# netCPU_breakout.net
KiCad netlist of a schematic drawn in EAGLE
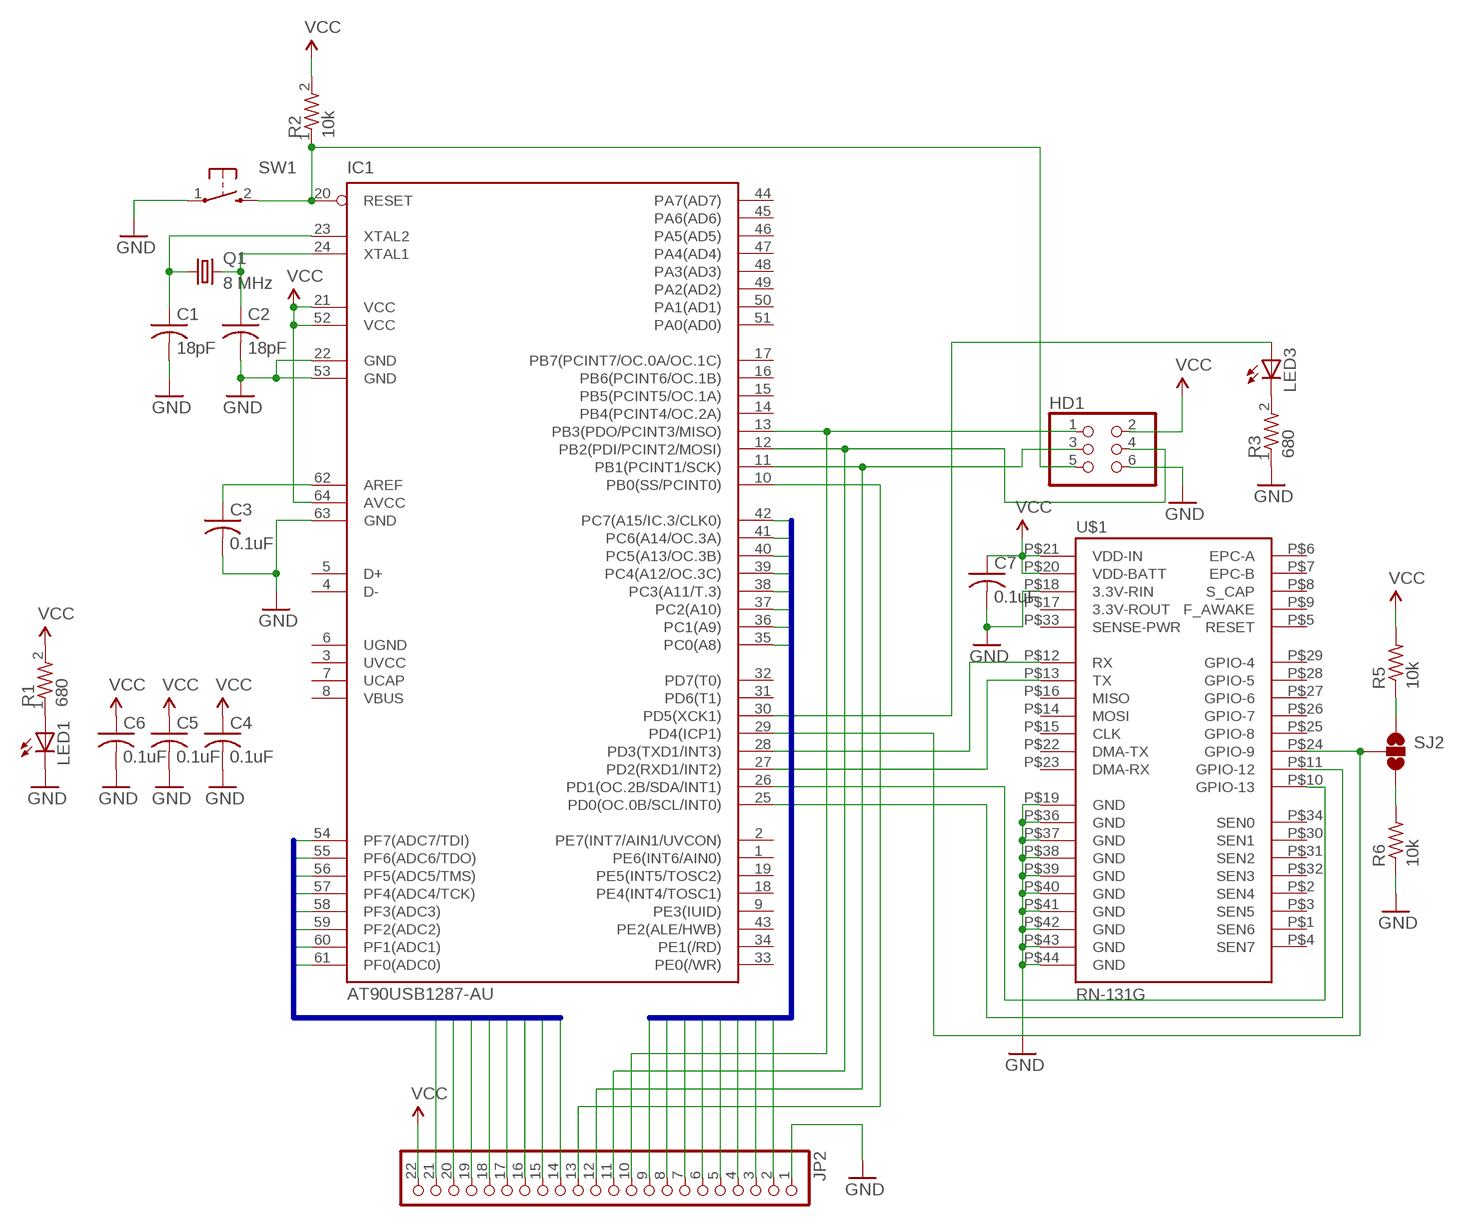
[diagram p0: schematic, sheet 1]

(export (version "E")
  (design (tool "Eeschema 10.0.6"))
  (components
    (comp (ref "C1")
      (value "18pF")
      (footprint "eagle-import:C0603K")
      (libsource (lib "eagle-import") (part "C-USC0603K"))
    )
    (comp (ref "C2")
      (value "18pF")
      (footprint "eagle-import:C0603K")
      (libsource (lib "eagle-import") (part "C-USC0603K"))
    )
    (comp (ref "C3")
      (value "0.1uF")
      (footprint "eagle-import:C0603K")
      (libsource (lib "eagle-import") (part "C-USC0603K"))
    )
    (comp (ref "C4")
      (value "0.1uF")
      (footprint "eagle-import:C0603K")
      (libsource (lib "eagle-import") (part "C-USC0603K"))
    )
    (comp (ref "C5")
      (value "0.1uF")
      (footprint "eagle-import:C0603K")
      (libsource (lib "eagle-import") (part "C-USC0603K"))
    )
    (comp (ref "C6")
      (value "0.1uF")
      (footprint "eagle-import:C0603K")
      (libsource (lib "eagle-import") (part "C-USC0603K"))
    )
    (comp (ref "C7")
      (value "0.1uF")
      (footprint "eagle-import:C0603K")
      (libsource (lib "eagle-import") (part "C-USC0603K"))
    )
    (comp (ref "HD1")
      (value "HEADER2X3")
      (footprint "eagle-import:HEADER2X3")
      (libsource (lib "eagle-import") (part "HEADER2X3"))
    )
    (comp (ref "IC1")
      (value "AT90USB1287-AU")
      (footprint "eagle-import:TQFP64")
      (libsource (lib "eagle-import") (part "AT90USB1287-AU"))
    )
    (comp (ref "JP2")
      (value "PINHD-1X22")
      (footprint "eagle-import:1X22")
      (libsource (lib "eagle-import") (part "PINHD-1X22"))
    )
    (comp (ref "LED1")
      (value "LEDCHIP-LED0603")
      (footprint "eagle-import:CHIP-LED0603")
      (libsource (lib "eagle-import") (part "LEDCHIP-LED0603"))
    )
    (comp (ref "LED3")
      (value "LEDCHIP-LED0603")
      (footprint "eagle-import:CHIP-LED0603")
      (libsource (lib "eagle-import") (part "LEDCHIP-LED0603"))
    )
    (comp (ref "Q1")
      (value "8 MHz")
      (footprint "eagle-import:HC49UP")
      (libsource (lib "eagle-import") (part "CRYSTALHC49UP"))
    )
    (comp (ref "R1")
      (value "680")
      (footprint "eagle-import:0603_RESISTOR")
      (libsource (lib "eagle-import") (part "0603_RESISTOR"))
    )
    (comp (ref "R2")
      (value "10k")
      (footprint "eagle-import:0603_RESISTOR")
      (libsource (lib "eagle-import") (part "0603_RESISTOR"))
    )
    (comp (ref "R3")
      (value "680")
      (footprint "eagle-import:0603_RESISTOR")
      (libsource (lib "eagle-import") (part "0603_RESISTOR"))
    )
    (comp (ref "R5")
      (value "10k")
      (footprint "eagle-import:R0603")
      (libsource (lib "eagle-import") (part "R-US_R0603"))
    )
    (comp (ref "R6")
      (value "10k")
      (footprint "eagle-import:R0603")
      (libsource (lib "eagle-import") (part "R-US_R0603"))
    )
    (comp (ref "SJ2")
      (value "SOLDERJUMPER_2WAYPASTE2&3")
      (footprint "eagle-import:SJ_3_PASTE2&3")
      (libsource (lib "eagle-import") (part "SOLDERJUMPER_2WAYPASTE2&3"))
    )
    (comp (ref "SW1")
      (value "TAC-SWITCH")
      (footprint "eagle-import:TAC-SWITCH")
      (libsource (lib "eagle-import") (part "TAC-SWITCH"))
    )
    (comp (ref "U$1")
      (value "RN-131G")
      (footprint "eagle-import:RN-131G")
      (libsource (lib "eagle-import") (part "RN-131G"))
    )
  )
  (nets
    (net (code "1") (name "/PC0") (class "Default")
      (node (ref "IC1") (pin "35") (pinfunction "PC0(A8)_35") (pintype "bidirectional"))
      (node (ref "JP2") (pin "2") (pinfunction "2_2") (pintype "passive"))
    )
    (net (code "2") (name "/PC1") (class "Default")
      (node (ref "IC1") (pin "36") (pinfunction "PC1(A9)_36") (pintype "bidirectional"))
      (node (ref "JP2") (pin "3") (pinfunction "3_3") (pintype "passive"))
    )
    (net (code "3") (name "/PC2") (class "Default")
      (node (ref "IC1") (pin "37") (pinfunction "PC2(A10)_37") (pintype "bidirectional"))
      (node (ref "JP2") (pin "4") (pinfunction "4_4") (pintype "passive"))
    )
    (net (code "4") (name "/PC3") (class "Default")
      (node (ref "IC1") (pin "38") (pinfunction "PC3(A11/T.3)_38") (pintype "bidirectional"))
      (node (ref "JP2") (pin "5") (pinfunction "5_5") (pintype "passive"))
    )
    (net (code "5") (name "/PC4") (class "Default")
      (node (ref "IC1") (pin "39") (pinfunction "PC4(A12/OC.3C)_39") (pintype "bidirectional"))
      (node (ref "JP2") (pin "6") (pinfunction "6_6") (pintype "passive"))
    )
    (net (code "6") (name "/PC5") (class "Default")
      (node (ref "IC1") (pin "40") (pinfunction "PC5(A13/OC.3B)_40") (pintype "bidirectional"))
      (node (ref "JP2") (pin "7") (pinfunction "7_7") (pintype "passive"))
    )
    (net (code "7") (name "/PC6") (class "Default")
      (node (ref "IC1") (pin "41") (pinfunction "PC6(A14/OC.3A)_41") (pintype "bidirectional"))
      (node (ref "JP2") (pin "8") (pinfunction "8_8") (pintype "passive"))
    )
    (net (code "8") (name "/PC7") (class "Default")
      (node (ref "IC1") (pin "42") (pinfunction "PC7(A15/IC.3/CLK0)_42") (pintype "bidirectional"))
      (node (ref "JP2") (pin "9") (pinfunction "9_9") (pintype "passive"))
    )
    (net (code "9") (name "/PF0") (class "Default")
      (node (ref "IC1") (pin "61") (pinfunction "PF0(ADC0)_61") (pintype "bidirectional"))
      (node (ref "JP2") (pin "14") (pinfunction "14_14") (pintype "passive"))
    )
    (net (code "10") (name "/PF1") (class "Default")
      (node (ref "IC1") (pin "60") (pinfunction "PF1(ADC1)_60") (pintype "bidirectional"))
      (node (ref "JP2") (pin "15") (pinfunction "15_15") (pintype "passive"))
    )
    (net (code "11") (name "/PF2") (class "Default")
      (node (ref "IC1") (pin "59") (pinfunction "PF2(ADC2)_59") (pintype "bidirectional"))
      (node (ref "JP2") (pin "16") (pinfunction "16_16") (pintype "passive"))
    )
    (net (code "12") (name "/PF3") (class "Default")
      (node (ref "IC1") (pin "58") (pinfunction "PF3(ADC3)_58") (pintype "bidirectional"))
      (node (ref "JP2") (pin "17") (pinfunction "17_17") (pintype "passive"))
    )
    (net (code "13") (name "/PF4") (class "Default")
      (node (ref "IC1") (pin "57") (pinfunction "PF4(ADC4/TCK)_57") (pintype "bidirectional"))
      (node (ref "JP2") (pin "18") (pinfunction "18_18") (pintype "passive"))
    )
    (net (code "14") (name "/PF5") (class "Default")
      (node (ref "IC1") (pin "56") (pinfunction "PF5(ADC5/TMS)_56") (pintype "bidirectional"))
      (node (ref "JP2") (pin "19") (pinfunction "19_19") (pintype "passive"))
    )
    (net (code "15") (name "/PF6") (class "Default")
      (node (ref "IC1") (pin "55") (pinfunction "PF6(ADC6/TDO)_55") (pintype "bidirectional"))
      (node (ref "JP2") (pin "20") (pinfunction "20_20") (pintype "passive"))
    )
    (net (code "16") (name "/PF7") (class "Default")
      (node (ref "IC1") (pin "54") (pinfunction "PF7(ADC7/TDI)_54") (pintype "bidirectional"))
      (node (ref "JP2") (pin "21") (pinfunction "21_21") (pintype "passive"))
    )
    (net (code "17") (name "/UCAP") (class "Default")
      (node (ref "IC1") (pin "7") (pinfunction "UCAP_7") (pintype "power_in"))
    )
    (net (code "18") (name "/UGND") (class "Default")
      (node (ref "IC1") (pin "6") (pinfunction "UGND_6") (pintype "power_in"))
    )
    (net (code "19") (name "/UVCC") (class "Default")
      (node (ref "IC1") (pin "3") (pinfunction "UVCC_3") (pintype "power_in"))
    )
    (net (code "20") (name "/VBUS") (class "Default")
      (node (ref "IC1") (pin "8") (pinfunction "VBUS_8") (pintype "power_in"))
    )
    (net (code "21") (name "GND") (class "Default")
      (node (ref "C1") (pin "2") (pinfunction "2_2") (pintype "passive"))
      (node (ref "C2") (pin "2") (pinfunction "2_2") (pintype "passive"))
      (node (ref "C3") (pin "2") (pinfunction "2_2") (pintype "passive"))
      (node (ref "C4") (pin "2") (pinfunction "2_2") (pintype "passive"))
      (node (ref "C5") (pin "2") (pinfunction "2_2") (pintype "passive"))
      (node (ref "C6") (pin "2") (pinfunction "2_2") (pintype "passive"))
      (node (ref "C7") (pin "2") (pinfunction "2_2") (pintype "passive"))
      (node (ref "HD1") (pin "6") (pinfunction "6_6") (pintype "passive"))
      (node (ref "IC1") (pin "22") (pinfunction "GND_22") (pintype "power_in"))
      (node (ref "IC1") (pin "53") (pinfunction "GND_53") (pintype "power_in"))
      (node (ref "IC1") (pin "63") (pinfunction "GND_63") (pintype "power_in"))
      (node (ref "JP2") (pin "1") (pinfunction "1_1") (pintype "passive"))
      (node (ref "LED1") (pin "C") (pinfunction "C_C") (pintype "passive"))
      (node (ref "R3") (pin "1") (pinfunction "1_1") (pintype "passive"))
      (node (ref "R6") (pin "1") (pinfunction "1_1") (pintype "passive"))
      (node (ref "SW1") (pin "1") (pinfunction "1_1") (pintype "passive"))
      (node (ref "U$1") (pin "P$18") (pinfunction "3.3V-RIN_P$18") (pintype "bidirectional"))
      (node (ref "U$1") (pin "P$19") (pinfunction "GND_P$19") (pintype "bidirectional"))
      (node (ref "U$1") (pin "P$36") (pinfunction "GND_P$36") (pintype "bidirectional"))
      (node (ref "U$1") (pin "P$37") (pinfunction "GND_P$37") (pintype "bidirectional"))
      (node (ref "U$1") (pin "P$38") (pinfunction "GND_P$38") (pintype "bidirectional"))
      (node (ref "U$1") (pin "P$39") (pinfunction "GND_P$39") (pintype "bidirectional"))
      (node (ref "U$1") (pin "P$40") (pinfunction "GND_P$40") (pintype "bidirectional"))
      (node (ref "U$1") (pin "P$41") (pinfunction "GND_P$41") (pintype "bidirectional"))
      (node (ref "U$1") (pin "P$42") (pinfunction "GND_P$42") (pintype "bidirectional"))
      (node (ref "U$1") (pin "P$43") (pinfunction "GND_P$43") (pintype "bidirectional"))
      (node (ref "U$1") (pin "P$44") (pinfunction "GND_P$44") (pintype "bidirectional"))
    )
    (net (code "22") (name "Net-(IC1-AREF)") (class "Default")
      (node (ref "C3") (pin "1") (pinfunction "1_1") (pintype "passive"))
      (node (ref "IC1") (pin "62") (pinfunction "AREF_62") (pintype "bidirectional"))
    )
    (net (code "23") (name "Net-(IC1-PB0(SS{slash}PCINT0))") (class "Default")
      (node (ref "IC1") (pin "10") (pinfunction "PB0(SS/PCINT0)_10") (pintype "bidirectional"))
      (node (ref "JP2") (pin "13") (pinfunction "13_13") (pintype "passive"))
    )
    (net (code "24") (name "Net-(IC1-PB1(PCINT1{slash}SCK))") (class "Default")
      (node (ref "HD1") (pin "3") (pinfunction "3_3") (pintype "passive"))
      (node (ref "IC1") (pin "11") (pinfunction "PB1(PCINT1/SCK)_11") (pintype "bidirectional"))
      (node (ref "JP2") (pin "12") (pinfunction "12_12") (pintype "passive"))
    )
    (net (code "25") (name "Net-(IC1-PB2(PDI{slash}PCINT2{slash}MOSI))") (class "Default")
      (node (ref "HD1") (pin "4") (pinfunction "4_4") (pintype "passive"))
      (node (ref "IC1") (pin "12") (pinfunction "PB2(PDI/PCINT2/MOSI)_12") (pintype "bidirectional"))
      (node (ref "JP2") (pin "11") (pinfunction "11_11") (pintype "passive"))
    )
    (net (code "26") (name "Net-(IC1-PB3(PDO{slash}PCINT3{slash}MISO))") (class "Default")
      (node (ref "HD1") (pin "1") (pinfunction "1_1") (pintype "passive"))
      (node (ref "IC1") (pin "13") (pinfunction "PB3(PDO/PCINT3/MISO)_13") (pintype "bidirectional"))
      (node (ref "JP2") (pin "10") (pinfunction "10_10") (pintype "passive"))
    )
    (net (code "27") (name "Net-(IC1-PD0(OC.0B{slash}SCL{slash}INT0))") (class "Default")
      (node (ref "IC1") (pin "25") (pinfunction "PD0(OC.0B/SCL/INT0)_25") (pintype "bidirectional"))
      (node (ref "U$1") (pin "P$11") (pinfunction "GPIO-12_P$11") (pintype "bidirectional"))
    )
    (net (code "28") (name "Net-(IC1-PD1(OC.2B{slash}SDA{slash}INT1))") (class "Default")
      (node (ref "IC1") (pin "26") (pinfunction "PD1(OC.2B/SDA/INT1)_26") (pintype "bidirectional"))
      (node (ref "U$1") (pin "P$10") (pinfunction "GPIO-13_P$10") (pintype "bidirectional"))
    )
    (net (code "29") (name "Net-(IC1-PD2(RXD1{slash}INT2))") (class "Default")
      (node (ref "IC1") (pin "27") (pinfunction "PD2(RXD1/INT2)_27") (pintype "bidirectional"))
      (node (ref "U$1") (pin "P$13") (pinfunction "TX_P$13") (pintype "bidirectional"))
    )
    (net (code "30") (name "Net-(IC1-PD3(TXD1{slash}INT3))") (class "Default")
      (node (ref "IC1") (pin "28") (pinfunction "PD3(TXD1/INT3)_28") (pintype "bidirectional"))
      (node (ref "U$1") (pin "P$12") (pinfunction "RX_P$12") (pintype "bidirectional"))
    )
    (net (code "31") (name "Net-(IC1-PD4(ICP1))") (class "Default")
      (node (ref "IC1") (pin "29") (pinfunction "PD4(ICP1)_29") (pintype "bidirectional"))
      (node (ref "SJ2") (pin "2") (pinfunction "2_2") (pintype "passive"))
      (node (ref "U$1") (pin "P$24") (pinfunction "GPIO-9_P$24") (pintype "bidirectional"))
    )
    (net (code "32") (name "Net-(IC1-PD5(XCK1))") (class "Default")
      (node (ref "IC1") (pin "30") (pinfunction "PD5(XCK1)_30") (pintype "bidirectional"))
      (node (ref "LED3") (pin "A") (pinfunction "A_A") (pintype "passive"))
    )
    (net (code "33") (name "Net-(IC1-RESET)") (class "Default")
      (node (ref "HD1") (pin "5") (pinfunction "5_5") (pintype "passive"))
      (node (ref "IC1") (pin "20") (pinfunction "RESET_20") (pintype "input"))
      (node (ref "R2") (pin "1") (pinfunction "1_1") (pintype "passive"))
      (node (ref "SW1") (pin "2") (pinfunction "2_2") (pintype "passive"))
    )
    (net (code "34") (name "Net-(IC1-XTAL1)") (class "Default")
      (node (ref "C2") (pin "1") (pinfunction "1_1") (pintype "passive"))
      (node (ref "IC1") (pin "24") (pinfunction "XTAL1_24") (pintype "bidirectional"))
      (node (ref "Q1") (pin "2") (pinfunction "2_2") (pintype "passive"))
    )
    (net (code "35") (name "Net-(IC1-XTAL2)") (class "Default")
      (node (ref "C1") (pin "1") (pinfunction "1_1") (pintype "passive"))
      (node (ref "IC1") (pin "23") (pinfunction "XTAL2_23") (pintype "bidirectional"))
      (node (ref "Q1") (pin "1") (pinfunction "1_1") (pintype "passive"))
    )
    (net (code "36") (name "Net-(LED1-PadA)") (class "Default")
      (node (ref "LED1") (pin "A") (pinfunction "A_A") (pintype "passive"))
      (node (ref "R1") (pin "1") (pinfunction "1_1") (pintype "passive"))
    )
    (net (code "37") (name "Net-(LED3-PadC)") (class "Default")
      (node (ref "LED3") (pin "C") (pinfunction "C_C") (pintype "passive"))
      (node (ref "R3") (pin "2") (pinfunction "2_2") (pintype "passive"))
    )
    (net (code "38") (name "Net-(R5-Pad1)") (class "Default")
      (node (ref "R5") (pin "1") (pinfunction "1_1") (pintype "passive"))
      (node (ref "SJ2") (pin "1") (pinfunction "1_1") (pintype "passive"))
    )
    (net (code "39") (name "Net-(R6-Pad2)") (class "Default")
      (node (ref "R6") (pin "2") (pinfunction "2_2") (pintype "passive"))
      (node (ref "SJ2") (pin "3") (pinfunction "3_3") (pintype "passive"))
    )
    (net (code "40") (name "VCC") (class "Default")
      (node (ref "C4") (pin "1") (pinfunction "1_1") (pintype "passive"))
      (node (ref "C5") (pin "1") (pinfunction "1_1") (pintype "passive"))
      (node (ref "C6") (pin "1") (pinfunction "1_1") (pintype "passive"))
      (node (ref "C7") (pin "1") (pinfunction "1_1") (pintype "passive"))
      (node (ref "HD1") (pin "2") (pinfunction "2_2") (pintype "passive"))
      (node (ref "IC1") (pin "21") (pinfunction "VCC_21") (pintype "power_in"))
      (node (ref "IC1") (pin "52") (pinfunction "VCC_52") (pintype "power_in"))
      (node (ref "IC1") (pin "64") (pinfunction "AVCC_64") (pintype "bidirectional"))
      (node (ref "JP2") (pin "22") (pinfunction "22_22") (pintype "passive"))
      (node (ref "R1") (pin "2") (pinfunction "2_2") (pintype "passive"))
      (node (ref "R2") (pin "2") (pinfunction "2_2") (pintype "passive"))
      (node (ref "R5") (pin "2") (pinfunction "2_2") (pintype "passive"))
      (node (ref "U$1") (pin "P$20") (pinfunction "VDD-BATT_P$20") (pintype "bidirectional"))
      (node (ref "U$1") (pin "P$21") (pinfunction "VDD-IN_P$21") (pintype "bidirectional"))
    )
    (net (code "41") (name "unconnected-(IC1-D+-Pad5)") (class "Default")
      (node (ref "IC1") (pin "5") (pinfunction "D+_5") (pintype "bidirectional"))
    )
    (net (code "42") (name "unconnected-(IC1-D--Pad4)") (class "Default")
      (node (ref "IC1") (pin "4") (pinfunction "D-_4") (pintype "bidirectional"))
    )
    (net (code "43") (name "unconnected-(IC1-PA0(AD0)-Pad51)") (class "Default")
      (node (ref "IC1") (pin "51") (pinfunction "PA0(AD0)_51") (pintype "bidirectional"))
    )
    (net (code "44") (name "unconnected-(IC1-PA1(AD1)-Pad50)") (class "Default")
      (node (ref "IC1") (pin "50") (pinfunction "PA1(AD1)_50") (pintype "bidirectional"))
    )
    (net (code "45") (name "unconnected-(IC1-PA2(AD2)-Pad49)") (class "Default")
      (node (ref "IC1") (pin "49") (pinfunction "PA2(AD2)_49") (pintype "bidirectional"))
    )
    (net (code "46") (name "unconnected-(IC1-PA3(AD3)-Pad48)") (class "Default")
      (node (ref "IC1") (pin "48") (pinfunction "PA3(AD3)_48") (pintype "bidirectional"))
    )
    (net (code "47") (name "unconnected-(IC1-PA4(AD4)-Pad47)") (class "Default")
      (node (ref "IC1") (pin "47") (pinfunction "PA4(AD4)_47") (pintype "bidirectional"))
    )
    (net (code "48") (name "unconnected-(IC1-PA5(AD5)-Pad46)") (class "Default")
      (node (ref "IC1") (pin "46") (pinfunction "PA5(AD5)_46") (pintype "bidirectional"))
    )
    (net (code "49") (name "unconnected-(IC1-PA6(AD6)-Pad45)") (class "Default")
      (node (ref "IC1") (pin "45") (pinfunction "PA6(AD6)_45") (pintype "bidirectional"))
    )
    (net (code "50") (name "unconnected-(IC1-PA7(AD7)-Pad44)") (class "Default")
      (node (ref "IC1") (pin "44") (pinfunction "PA7(AD7)_44") (pintype "bidirectional"))
    )
    (net (code "51") (name "unconnected-(IC1-PB4(PCINT4{slash}OC.2A)-Pad14)") (class "Default")
      (node (ref "IC1") (pin "14") (pinfunction "PB4(PCINT4/OC.2A)_14") (pintype "bidirectional"))
    )
    (net (code "52") (name "unconnected-(IC1-PB5(PCINT5{slash}OC.1A)-Pad15)") (class "Default")
      (node (ref "IC1") (pin "15") (pinfunction "PB5(PCINT5/OC.1A)_15") (pintype "bidirectional"))
    )
    (net (code "53") (name "unconnected-(IC1-PB6(PCINT6{slash}OC.1B)-Pad16)") (class "Default")
      (node (ref "IC1") (pin "16") (pinfunction "PB6(PCINT6/OC.1B)_16") (pintype "bidirectional"))
    )
    (net (code "54") (name "unconnected-(IC1-PB7(PCINT7{slash}OC.0A{slash}OC.1C)-Pad17)") (class "Default")
      (node (ref "IC1") (pin "17") (pinfunction "PB7(PCINT7/OC.0A/OC.1C)_17") (pintype "bidirectional"))
    )
    (net (code "55") (name "unconnected-(IC1-PD6(T1)-Pad31)") (class "Default")
      (node (ref "IC1") (pin "31") (pinfunction "PD6(T1)_31") (pintype "bidirectional"))
    )
    (net (code "56") (name "unconnected-(IC1-PD7(T0)-Pad32)") (class "Default")
      (node (ref "IC1") (pin "32") (pinfunction "PD7(T0)_32") (pintype "bidirectional"))
    )
    (net (code "57") (name "unconnected-(IC1-PE0({slash}WR)-Pad33)") (class "Default")
      (node (ref "IC1") (pin "33") (pinfunction "PE0(/WR)_33") (pintype "bidirectional"))
    )
    (net (code "58") (name "unconnected-(IC1-PE1({slash}RD)-Pad34)") (class "Default")
      (node (ref "IC1") (pin "34") (pinfunction "PE1(/RD)_34") (pintype "bidirectional"))
    )
    (net (code "59") (name "unconnected-(IC1-PE2(ALE{slash}HWB)-Pad43)") (class "Default")
      (node (ref "IC1") (pin "43") (pinfunction "PE2(ALE/HWB)_43") (pintype "bidirectional"))
    )
    (net (code "60") (name "unconnected-(IC1-PE3(IUID)-Pad9)") (class "Default")
      (node (ref "IC1") (pin "9") (pinfunction "PE3(IUID)_9") (pintype "bidirectional"))
    )
    (net (code "61") (name "unconnected-(IC1-PE4(INT4{slash}TOSC1)-Pad18)") (class "Default")
      (node (ref "IC1") (pin "18") (pinfunction "PE4(INT4/TOSC1)_18") (pintype "bidirectional"))
    )
    (net (code "62") (name "unconnected-(IC1-PE5(INT5{slash}TOSC2)-Pad19)") (class "Default")
      (node (ref "IC1") (pin "19") (pinfunction "PE5(INT5/TOSC2)_19") (pintype "bidirectional"))
    )
    (net (code "63") (name "unconnected-(IC1-PE6(INT6{slash}AIN0)-Pad1)") (class "Default")
      (node (ref "IC1") (pin "1") (pinfunction "PE6(INT6/AIN0)_1") (pintype "bidirectional"))
    )
    (net (code "64") (name "unconnected-(IC1-PE7(INT7{slash}AIN1{slash}UVCON)-Pad2)") (class "Default")
      (node (ref "IC1") (pin "2") (pinfunction "PE7(INT7/AIN1/UVCON)_2") (pintype "bidirectional"))
    )
    (net (code "65") (name "unconnected-(U$1-3.3V-ROUT-PadP$17)") (class "Default")
      (node (ref "U$1") (pin "P$17") (pinfunction "3.3V-ROUT_P$17") (pintype "bidirectional"))
    )
    (net (code "66") (name "unconnected-(U$1-CLK-PadP$15)") (class "Default")
      (node (ref "U$1") (pin "P$15") (pinfunction "CLK_P$15") (pintype "bidirectional"))
    )
    (net (code "67") (name "unconnected-(U$1-DMA-RX-PadP$23)") (class "Default")
      (node (ref "U$1") (pin "P$23") (pinfunction "DMA-RX_P$23") (pintype "bidirectional"))
    )
    (net (code "68") (name "unconnected-(U$1-DMA-TX-PadP$22)") (class "Default")
      (node (ref "U$1") (pin "P$22") (pinfunction "DMA-TX_P$22") (pintype "bidirectional"))
    )
    (net (code "69") (name "unconnected-(U$1-EPC-A-PadP$6)") (class "Default")
      (node (ref "U$1") (pin "P$6") (pinfunction "EPC-A_P$6") (pintype "bidirectional"))
    )
    (net (code "70") (name "unconnected-(U$1-EPC-B-PadP$7)") (class "Default")
      (node (ref "U$1") (pin "P$7") (pinfunction "EPC-B_P$7") (pintype "bidirectional"))
    )
    (net (code "71") (name "unconnected-(U$1-F_AWAKE-PadP$9)") (class "Default")
      (node (ref "U$1") (pin "P$9") (pinfunction "F_AWAKE_P$9") (pintype "bidirectional"))
    )
    (net (code "72") (name "unconnected-(U$1-GPIO-4-PadP$29)") (class "Default")
      (node (ref "U$1") (pin "P$29") (pinfunction "GPIO-4_P$29") (pintype "bidirectional"))
    )
    (net (code "73") (name "unconnected-(U$1-GPIO-5-PadP$28)") (class "Default")
      (node (ref "U$1") (pin "P$28") (pinfunction "GPIO-5_P$28") (pintype "bidirectional"))
    )
    (net (code "74") (name "unconnected-(U$1-GPIO-6-PadP$27)") (class "Default")
      (node (ref "U$1") (pin "P$27") (pinfunction "GPIO-6_P$27") (pintype "bidirectional"))
    )
    (net (code "75") (name "unconnected-(U$1-GPIO-7-PadP$26)") (class "Default")
      (node (ref "U$1") (pin "P$26") (pinfunction "GPIO-7_P$26") (pintype "bidirectional"))
    )
    (net (code "76") (name "unconnected-(U$1-GPIO-8-PadP$25)") (class "Default")
      (node (ref "U$1") (pin "P$25") (pinfunction "GPIO-8_P$25") (pintype "bidirectional"))
    )
    (net (code "77") (name "unconnected-(U$1-MISO-PadP$16)") (class "Default")
      (node (ref "U$1") (pin "P$16") (pinfunction "MISO_P$16") (pintype "bidirectional"))
    )
    (net (code "78") (name "unconnected-(U$1-MOSI-PadP$14)") (class "Default")
      (node (ref "U$1") (pin "P$14") (pinfunction "MOSI_P$14") (pintype "bidirectional"))
    )
    (net (code "79") (name "unconnected-(U$1-RESET-PadP$5)") (class "Default")
      (node (ref "U$1") (pin "P$5") (pinfunction "RESET_P$5") (pintype "bidirectional"))
    )
    (net (code "80") (name "unconnected-(U$1-SEN0-PadP$34)") (class "Default")
      (node (ref "U$1") (pin "P$34") (pinfunction "SEN0_P$34") (pintype "bidirectional"))
    )
    (net (code "81") (name "unconnected-(U$1-SEN1-PadP$30)") (class "Default")
      (node (ref "U$1") (pin "P$30") (pinfunction "SEN1_P$30") (pintype "bidirectional"))
    )
    (net (code "82") (name "unconnected-(U$1-SEN2-PadP$31)") (class "Default")
      (node (ref "U$1") (pin "P$31") (pinfunction "SEN2_P$31") (pintype "bidirectional"))
    )
    (net (code "83") (name "unconnected-(U$1-SEN3-PadP$32)") (class "Default")
      (node (ref "U$1") (pin "P$32") (pinfunction "SEN3_P$32") (pintype "bidirectional"))
    )
    (net (code "84") (name "unconnected-(U$1-SEN4-PadP$2)") (class "Default")
      (node (ref "U$1") (pin "P$2") (pinfunction "SEN4_P$2") (pintype "bidirectional"))
    )
    (net (code "85") (name "unconnected-(U$1-SEN5-PadP$3)") (class "Default")
      (node (ref "U$1") (pin "P$3") (pinfunction "SEN5_P$3") (pintype "bidirectional"))
    )
    (net (code "86") (name "unconnected-(U$1-SEN6-PadP$1)") (class "Default")
      (node (ref "U$1") (pin "P$1") (pinfunction "SEN6_P$1") (pintype "bidirectional"))
    )
    (net (code "87") (name "unconnected-(U$1-SEN7-PadP$4)") (class "Default")
      (node (ref "U$1") (pin "P$4") (pinfunction "SEN7_P$4") (pintype "bidirectional"))
    )
    (net (code "88") (name "unconnected-(U$1-SENSE-PWR-PadP$33)") (class "Default")
      (node (ref "U$1") (pin "P$33") (pinfunction "SENSE-PWR_P$33") (pintype "bidirectional"))
    )
    (net (code "89") (name "unconnected-(U$1-S_CAP-PadP$8)") (class "Default")
      (node (ref "U$1") (pin "P$8") (pinfunction "S_CAP_P$8") (pintype "bidirectional"))
    )
  )
)
